# FanControllerSch_Rev2.net
KiCad netlist of a schematic drawn in Altium Designer
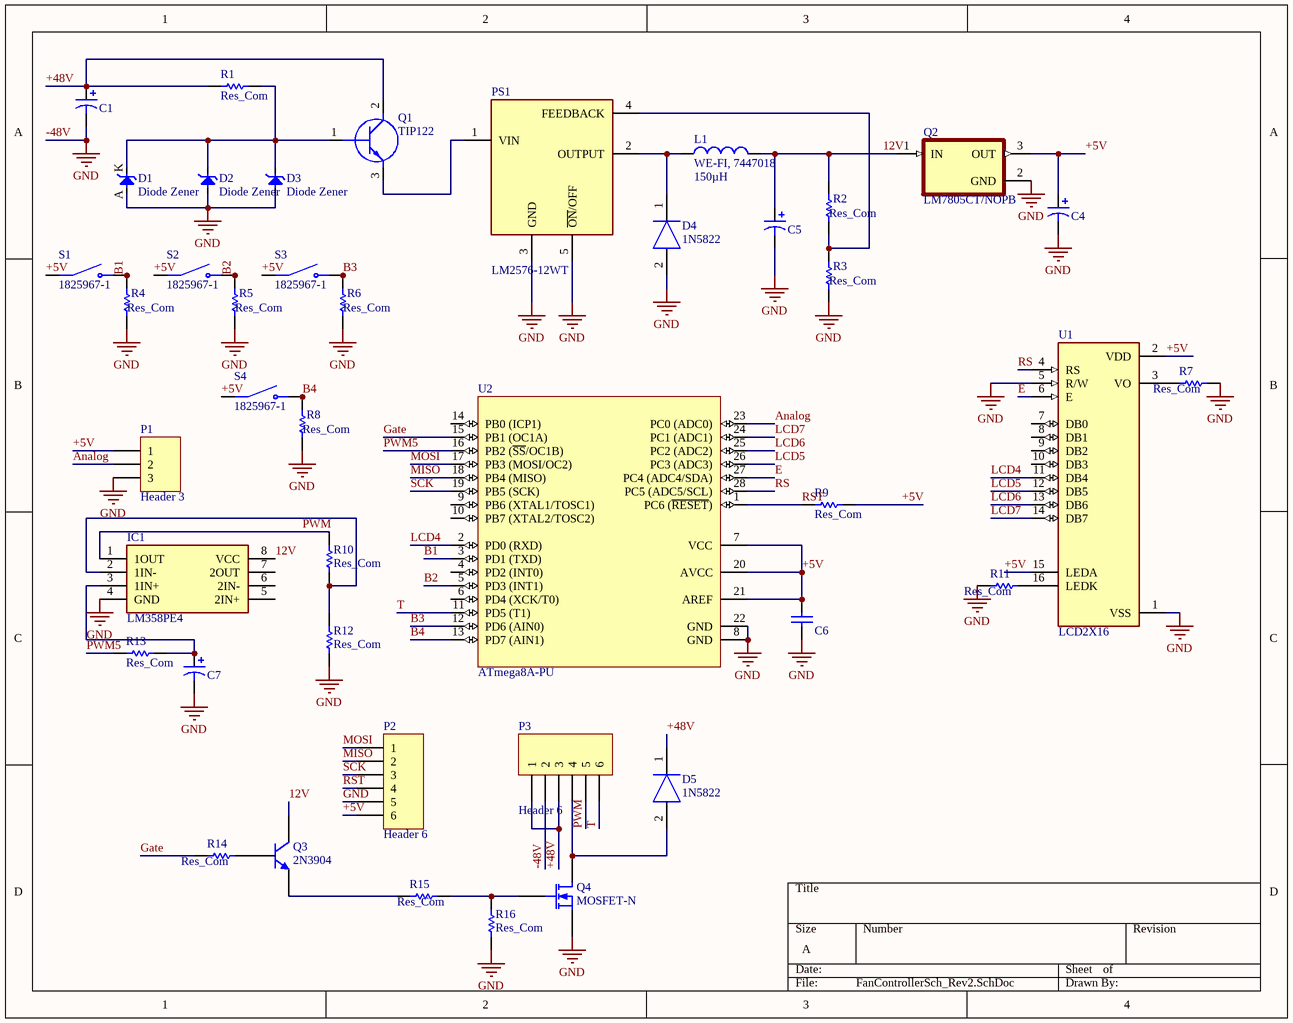
[diagram p0: FanControllerSch_Rev2.SchDoc]

(export (version "E")
  (design (tool "Eeschema 10.0.6"))
  (components
    (comp (ref "C1")
      (value "100 μF")
      (footprint "Radial 12.5 x 25")
      (description "Electrolitic Capacitor, Thru-Hole")
      (fields
        (field (name "PUBLISHER") "Cynetik Group")
        (field (name "CREATED BY") "Zion Blue")
        (field (name "CONTACT") "cynetik_group@hotmail.com")
      )
      (libsource (lib "Capacitors") (part "Electrolitic Capacitor, Thru-Hole"))
    )
    (comp (ref "C4")
      (value "100 μF")
      (footprint "RADIAL 3.5x7.7")
      (description "Electrolitic Capacitor, Thru-Hole")
      (fields
        (field (name "PUBLISHER") "Cynetik Group")
        (field (name "CREATED BY") "Zion Blue")
        (field (name "CONTACT") "cynetik_group@hotmail.com")
      )
      (libsource (lib "Capacitors") (part "Electrolitic Capacitor, Thru-Hole"))
    )
    (comp (ref "C5")
      (value "100 μF")
      (footprint "RADIAL 3.5x7.7")
      (description "Electrolitic Capacitor, Thru-Hole")
      (fields
        (field (name "PUBLISHER") "Cynetik Group")
        (field (name "CREATED BY") "Zion Blue")
        (field (name "CONTACT") "cynetik_group@hotmail.com")
      )
      (libsource (lib "Capacitors") (part "Electrolitic Capacitor, Thru-Hole"))
    )
    (comp (ref "C6")
      (value "100 nF")
      (footprint "Ceramic Capacitor 2")
      (description "Ceramic Capacitor, Thru-Hole")
      (fields
        (field (name "CREATED BY") "Zion Blue")
        (field (name "PUBLISHER") "Cynetik Group")
        (field (name "CONTACT") "cynetik_group@hotmail.com")
      )
      (libsource (lib "Capacitors") (part "Ceramic Capacitor, Thru-Hole."))
    )
    (comp (ref "C7")
      (value "100 μF")
      (footprint "RADIAL 3.5x7.7")
      (description "Electrolitic Capacitor, Thru-Hole")
      (fields
        (field (name "PUBLISHER") "Cynetik Group")
        (field (name "CREATED BY") "Zion Blue")
        (field (name "CONTACT") "cynetik_group@hotmail.com")
      )
      (libsource (lib "Capacitors") (part "Electrolitic Capacitor, Thru-Hole"))
    )
    (comp (ref "D1")
      (value "Diode Zener")
      (footprint "ONSC-AXIAL_LEAD-2-59-10_P")
      (libsource (lib "") (part "Diode Zener_1"))
    )
    (comp (ref "D2")
      (value "Diode Zener")
      (footprint "ONSC-AXIAL_LEAD-2-59-10_P")
      (libsource (lib "Diodes") (part "Diode Zener"))
    )
    (comp (ref "D3")
      (value "Diode Zener")
      (footprint "ONSC-AXIAL_LEAD-2-59-10_P")
      (libsource (lib "Diodes") (part "Diode Zener"))
    )
    (comp (ref "D4")
      (value "1N5822")
      (footprint "ONSC-AXIAL_LEAD-2-59-10_P")
      (description "Diode")
      (libsource (lib "*") (part "1N5822"))
    )
    (comp (ref "D5")
      (value "1N5822")
      (footprint "ONSC-AXIAL_LEAD-2-59-10_P")
      (description "Diode")
      (libsource (lib "*") (part "1N5822"))
    )
    (comp (ref "IC1")
      (value "LM358PE4")
      (footprint "SamacSys:DIP794W53P254L959H508Q8N")
      (description "Integrated Circuit")
      (fields (field (name "MOUSER PART NUMBER") "595-LM358PE4"))
      (libsource (lib "*") (part "LM358PE4"))
    )
    (comp (ref "L1")
      (value "WE-FI, 7447018")
      (footprint "TSL0709RA-102KR19-PF")
      (description "WE-FI Leaded Toroidal Line Choke, L = 150µH")
      (fields
        (field (name "PARTNO") "7447018")
        (field (name "MANUFACTURER") "Wurth Elektronik")
        (field (name "ALTIUM_VALUE") "150µH")
        (field (name "CREATED BY") "Baojun Chen")
      )
      (libsource (lib "Inductor") (part "WE-FI, 7447018"))
    )
    (comp (ref "P1")
      (value "Header 3")
      (footprint "HDR1X3")
      (description "Header, 3-Pin")
      (fields (field (name "PUBLISHER") "Altium Limited"))
      (libsource (lib "Miscellaneous Connectors") (part "Header 3"))
    )
    (comp (ref "P2")
      (value "Header 6")
      (footprint "HDR1X6")
      (description "Header, 6-Pin")
      (fields (field (name "PUBLISHER") "Altium Limited"))
      (libsource (lib "Miscellaneous Connectors") (part "Header 6"))
    )
    (comp (ref "P3")
      (value "Header 6")
      (footprint "HDR1X6")
      (description "Header, 6-Pin")
      (fields (field (name "PUBLISHER") "Altium Limited"))
      (libsource (lib "") (part "Header 6_1"))
    )
    (comp (ref "PS1")
      (value "LM2576-12WT")
      (footprint "SamacSys:TO170P470X1016X1900-5P")
      (description "Power Supply")
      (fields (field (name "MOUSER PART NUMBER") "998-LM2576-12WT"))
      (libsource (lib "*") (part "LM2576-12WT"))
    )
    (comp (ref "Q1")
      (value "TIP122")
      (footprint "SamacSys:TO255P460X1020X2008-3P")
      (description "Transistor BJT NPN")
      (fields (field (name "MOUSER PART NUMBER") "511-TIP122"))
      (libsource (lib "*") (part "TIP122"))
    )
    (comp (ref "Q2")
      (value "LM7805CT/NOPB")
      (footprint "TO254P1054X470X2600-3")
      (description "Linear Voltage Regulator IC 1 Output 1A TO-220-3")
      (fields (field (name "MP") "LM7805CT") (field (name "MF") "ON Semiconductor"))
      (libsource (lib "LDO") (part "LM7805CT/NOPB"))
    )
    (comp (ref "Q3")
      (value "2N3904")
      (footprint "TO-92A")
      (description "NPN General Purpose Amplifier")
      (fields (field (name "PUBLISHER") "Altium Limited"))
      (libsource (lib "Miscellaneous Devices") (part "2N3904"))
    )
    (comp (ref "Q4")
      (value "MOSFET-N")
      (footprint "TO-220AB")
      (description "N-Channel MOSFET")
      (fields (field (name "PUBLISHER") "Altium Limited"))
      (libsource (lib "Miscellaneous Devices") (part "MOSFET-N"))
    )
    (comp (ref "R1")
      (value "Res_Com")
      (footprint "1K Ohm")
      (libsource (lib "Resistors_SMD_IPC-SM-782") (part "Res_Com"))
    )
    (comp (ref "R2")
      (value "Res_Com")
      (footprint "1K Ohm")
      (libsource (lib "Resistors_SMD_IPC-SM-782") (part "Res_Com"))
    )
    (comp (ref "R3")
      (value "Res_Com")
      (footprint "1K Ohm")
      (libsource (lib "Resistors_SMD_IPC-SM-782") (part "Res_Com"))
    )
    (comp (ref "R4")
      (value "Res_Com")
      (footprint "1K Ohm")
      (libsource (lib "Resistors_SMD_IPC-SM-782") (part "Res_Com"))
    )
    (comp (ref "R5")
      (value "Res_Com")
      (footprint "1K Ohm")
      (libsource (lib "Resistors_SMD_IPC-SM-782") (part "Res_Com"))
    )
    (comp (ref "R6")
      (value "Res_Com")
      (footprint "1K Ohm")
      (libsource (lib "Resistors_SMD_IPC-SM-782") (part "Res_Com"))
    )
    (comp (ref "R7")
      (value "Res_Com")
      (footprint "1K Ohm")
      (libsource (lib "Resistors_SMD_IPC-SM-782") (part "Res_Com"))
    )
    (comp (ref "R8")
      (value "Res_Com")
      (footprint "1K Ohm")
      (libsource (lib "Resistors_SMD_IPC-SM-782") (part "Res_Com"))
    )
    (comp (ref "R9")
      (value "Res_Com")
      (footprint "1K Ohm")
      (libsource (lib "Resistors_SMD_IPC-SM-782") (part "Res_Com"))
    )
    (comp (ref "R10")
      (value "Res_Com")
      (footprint "1K Ohm")
      (libsource (lib "Resistors_SMD_IPC-SM-782") (part "Res_Com"))
    )
    (comp (ref "R11")
      (value "Res_Com")
      (footprint "1K Ohm")
      (libsource (lib "Resistors_SMD_IPC-SM-782") (part "Res_Com"))
    )
    (comp (ref "R12")
      (value "Res_Com")
      (footprint "1K Ohm")
      (libsource (lib "Resistors_SMD_IPC-SM-782") (part "Res_Com"))
    )
    (comp (ref "R13")
      (value "Res_Com")
      (footprint "1K Ohm")
      (libsource (lib "Resistors_SMD_IPC-SM-782") (part "Res_Com"))
    )
    (comp (ref "R14")
      (value "Res_Com")
      (footprint "1K Ohm")
      (libsource (lib "Resistors_SMD_IPC-SM-782") (part "Res_Com"))
    )
    (comp (ref "R15")
      (value "Res_Com")
      (footprint "1K Ohm")
      (libsource (lib "Resistors_SMD_IPC-SM-782") (part "Res_Com"))
    )
    (comp (ref "R16")
      (value "Res_Com")
      (footprint "1K Ohm")
      (libsource (lib "Resistors_SMD_IPC-SM-782") (part "Res_Com"))
    )
    (comp (ref "S1")
      (value "1825967-1")
      (footprint "SW_1825967-1")
      (description "Switch Tactile OFF (ON) SPST Round Button PC Pins 0.05A 24VDC 1.57N Thru-Hole")
      (fields
        (field (name "MF") "TE Connectivity")
        (field (name "BUYPART") "https://www.snapeda.com/parts/1825967-1/TE%20Connectivity%20/%20DEUTSCH/view-part/398388/?ref=eda")
      )
      (libsource (lib "1825967-1") (part "1825967-1"))
    )
    (comp (ref "S2")
      (value "1825967-1")
      (footprint "SW_1825967-1")
      (description "Switch Tactile OFF (ON) SPST Round Button PC Pins 0.05A 24VDC 1.57N Thru-Hole")
      (fields
        (field (name "MF") "TE Connectivity")
        (field (name "BUYPART") "https://www.snapeda.com/parts/1825967-1/TE%20Connectivity%20/%20DEUTSCH/view-part/398388/?ref=eda")
      )
      (libsource (lib "1825967-1") (part "1825967-1"))
    )
    (comp (ref "S3")
      (value "1825967-1")
      (footprint "SW_1825967-1")
      (description "Switch Tactile OFF (ON) SPST Round Button PC Pins 0.05A 24VDC 1.57N Thru-Hole")
      (fields
        (field (name "MF") "TE Connectivity")
        (field (name "BUYPART") "https://www.snapeda.com/parts/1825967-1/TE%20Connectivity%20/%20DEUTSCH/view-part/398388/?ref=eda")
      )
      (libsource (lib "1825967-1") (part "1825967-1"))
    )
    (comp (ref "S4")
      (value "1825967-1")
      (footprint "SW_1825967-1")
      (description "Switch Tactile OFF (ON) SPST Round Button PC Pins 0.05A 24VDC 1.57N Thru-Hole")
      (fields
        (field (name "MF") "TE Connectivity")
        (field (name "BUYPART") "https://www.snapeda.com/parts/1825967-1/TE%20Connectivity%20/%20DEUTSCH/view-part/398388/?ref=eda")
      )
      (libsource (lib "1825967-1") (part "1825967-1"))
    )
    (comp (ref "U1")
      (value "LCD2X16")
      (footprint "LCD_LCD2X16")
      (description "Display; Display: LCD 2x16 characters (blue backlight)")
      (fields (field (name "MF") "mikroElektronika"))
      (libsource (lib "LCD2X16") (part "LCD2X16"))
    )
    (comp (ref "U2") (value "ATmega8A-PU") (footprint "28P3") (libsource (lib "ICs") (part "ATmega8A-PU")))
  )
  (nets
    (net (code "1") (name "/+5V") (class "Default")
      (node (ref "C4") (pin "1") (pinfunction "1_1") (pintype "passive"))
      (node (ref "C6") (pin "2") (pinfunction "2_2") (pintype "passive"))
      (node (ref "P1") (pin "1") (pinfunction "1_1") (pintype "passive"))
      (node (ref "P2") (pin "6") (pinfunction "6_6") (pintype "passive"))
      (node (ref "Q2") (pin "3") (pinfunction "OUT_3") (pintype "output"))
      (node (ref "R9") (pin "2") (pinfunction "2_2") (pintype "passive"))
      (node (ref "S1") (pin "1") (pinfunction "COM_1") (pintype "passive"))
      (node (ref "S1") (pin "2") (pinfunction "COM_2") (pintype "passive"))
      (node (ref "S2") (pin "1") (pinfunction "COM_1") (pintype "passive"))
      (node (ref "S2") (pin "2") (pinfunction "COM_2") (pintype "passive"))
      (node (ref "S3") (pin "1") (pinfunction "COM_1") (pintype "passive"))
      (node (ref "S3") (pin "2") (pinfunction "COM_2") (pintype "passive"))
      (node (ref "S4") (pin "1") (pinfunction "COM_1") (pintype "passive"))
      (node (ref "S4") (pin "2") (pinfunction "COM_2") (pintype "passive"))
      (node (ref "U1") (pin "15") (pinfunction "LEDA_15") (pintype "passive"))
      (node (ref "U1") (pin "2") (pinfunction "VDD_2") (pintype "power_in"))
      (node (ref "U2") (pin "20") (pinfunction "AVCC_20") (pintype "power_in"))
      (node (ref "U2") (pin "21") (pinfunction "AREF_21") (pintype "passive"))
      (node (ref "U2") (pin "7") (pinfunction "VCC_7") (pintype "power_in"))
    )
    (net (code "2") (name "/+48V") (class "Default")
      (node (ref "C1") (pin "1") (pinfunction "1_1") (pintype "passive"))
      (node (ref "D5") (pin "1") (pinfunction "K_1") (pintype "passive"))
      (node (ref "P3") (pin "1") (pinfunction "1_1") (pintype "passive"))
      (node (ref "P3") (pin "3") (pinfunction "3_3") (pintype "passive"))
      (node (ref "Q1") (pin "2") (pinfunction "C_2") (pintype "passive"))
      (node (ref "R1") (pin "2") (pinfunction "2_2") (pintype "passive"))
    )
    (net (code "3") (name "/12V") (class "Default")
      (node (ref "C5") (pin "1") (pinfunction "1_1") (pintype "passive"))
      (node (ref "IC1") (pin "8") (pinfunction "VCC_8") (pintype "passive"))
      (node (ref "L1") (pin "2") (pinfunction "2_2") (pintype "passive"))
      (node (ref "Q2") (pin "1") (pinfunction "IN_1") (pintype "input"))
      (node (ref "Q3") (pin "3") (pinfunction "C_3") (pintype "passive"))
      (node (ref "R2") (pin "2") (pinfunction "2_2") (pintype "passive"))
    )
    (net (code "4") (name "/Analog") (class "Default")
      (node (ref "P1") (pin "2") (pinfunction "2_2") (pintype "passive"))
      (node (ref "U2") (pin "23") (pinfunction "PC0_(ADC0)_23") (pintype "bidirectional"))
    )
    (net (code "5") (name "/B1") (class "Default")
      (node (ref "R4") (pin "2") (pinfunction "2_2") (pintype "passive"))
      (node (ref "S1") (pin "3") (pinfunction "NO_3") (pintype "passive"))
      (node (ref "S1") (pin "4") (pinfunction "NO_4") (pintype "passive"))
      (node (ref "U2") (pin "3") (pinfunction "PD1_(TXD)_3") (pintype "bidirectional"))
    )
    (net (code "6") (name "/B2") (class "Default")
      (node (ref "R5") (pin "2") (pinfunction "2_2") (pintype "passive"))
      (node (ref "S2") (pin "3") (pinfunction "NO_3") (pintype "passive"))
      (node (ref "S2") (pin "4") (pinfunction "NO_4") (pintype "passive"))
      (node (ref "U2") (pin "5") (pinfunction "PD3_(INT1)_5") (pintype "bidirectional"))
    )
    (net (code "7") (name "/B3") (class "Default")
      (node (ref "R6") (pin "2") (pinfunction "2_2") (pintype "passive"))
      (node (ref "S3") (pin "3") (pinfunction "NO_3") (pintype "passive"))
      (node (ref "S3") (pin "4") (pinfunction "NO_4") (pintype "passive"))
      (node (ref "U2") (pin "12") (pinfunction "PD6_(AIN0)_12") (pintype "bidirectional"))
    )
    (net (code "8") (name "/B4") (class "Default")
      (node (ref "R8") (pin "2") (pinfunction "2_2") (pintype "passive"))
      (node (ref "S4") (pin "3") (pinfunction "NO_3") (pintype "passive"))
      (node (ref "S4") (pin "4") (pinfunction "NO_4") (pintype "passive"))
      (node (ref "U2") (pin "13") (pinfunction "PD7_(AIN1)_13") (pintype "bidirectional"))
    )
    (net (code "9") (name "/E") (class "Default")
      (node (ref "U1") (pin "6") (pinfunction "E_6") (pintype "input"))
      (node (ref "U2") (pin "27") (pinfunction "PC4_(ADC4/SDA)_27") (pintype "bidirectional"))
    )
    (net (code "10") (name "/Gate") (class "Default")
      (node (ref "R14") (pin "2") (pinfunction "2_2") (pintype "passive"))
      (node (ref "U2") (pin "15") (pinfunction "PB1_(OC1A)_15") (pintype "bidirectional"))
    )
    (net (code "11") (name "/LCD4") (class "Default")
      (node (ref "U1") (pin "11") (pinfunction "DB4_11") (pintype "bidirectional"))
      (node (ref "U2") (pin "2") (pinfunction "PD0_(RXD)_2") (pintype "bidirectional"))
    )
    (net (code "12") (name "/LCD5") (class "Default")
      (node (ref "U1") (pin "12") (pinfunction "DB5_12") (pintype "bidirectional"))
      (node (ref "U2") (pin "26") (pinfunction "PC3_(ADC3)_26") (pintype "bidirectional"))
    )
    (net (code "13") (name "/LCD6") (class "Default")
      (node (ref "U1") (pin "13") (pinfunction "DB6_13") (pintype "bidirectional"))
      (node (ref "U2") (pin "25") (pinfunction "PC2_(ADC2)_25") (pintype "bidirectional"))
    )
    (net (code "14") (name "/LCD7") (class "Default")
      (node (ref "U1") (pin "14") (pinfunction "DB7_14") (pintype "bidirectional"))
      (node (ref "U2") (pin "24") (pinfunction "PC1_(ADC1)_24") (pintype "bidirectional"))
    )
    (net (code "15") (name "/MISO") (class "Default")
      (node (ref "P2") (pin "2") (pinfunction "2_2") (pintype "passive"))
      (node (ref "U2") (pin "18") (pinfunction "PB4_(MISO)_18") (pintype "bidirectional"))
    )
    (net (code "16") (name "/MOSI") (class "Default")
      (node (ref "P2") (pin "1") (pinfunction "1_1") (pintype "passive"))
      (node (ref "U2") (pin "17") (pinfunction "PB3_(MOSI/OC2)_17") (pintype "bidirectional"))
    )
    (net (code "17") (name "/PWM") (class "Default")
      (node (ref "IC1") (pin "1") (pinfunction "1OUT_1") (pintype "passive"))
      (node (ref "P3") (pin "5") (pinfunction "5_5") (pintype "passive"))
      (node (ref "R10") (pin "1") (pinfunction "1_1") (pintype "passive"))
    )
    (net (code "18") (name "/PWM5") (class "Default")
      (node (ref "R13") (pin "2") (pinfunction "2_2") (pintype "passive"))
      (node (ref "U2") (pin "16") (pinfunction "PB2_(~{SS}/OC1B)_16") (pintype "bidirectional"))
    )
    (net (code "19") (name "/RS") (class "Default")
      (node (ref "U1") (pin "4") (pinfunction "RS_4") (pintype "input"))
      (node (ref "U2") (pin "28") (pinfunction "PC5_(ADC5/SCL)_28") (pintype "bidirectional"))
    )
    (net (code "20") (name "/RST") (class "Default")
      (node (ref "P2") (pin "4") (pinfunction "4_4") (pintype "passive"))
      (node (ref "R9") (pin "1") (pinfunction "1_1") (pintype "passive"))
      (node (ref "U2") (pin "1") (pinfunction "PC6_(~{RESET})_1") (pintype "bidirectional"))
    )
    (net (code "21") (name "/SCK") (class "Default")
      (node (ref "P2") (pin "3") (pinfunction "3_3") (pintype "passive"))
      (node (ref "U2") (pin "19") (pinfunction "PB5_(SCK)_19") (pintype "bidirectional"))
    )
    (net (code "22") (name "/T") (class "Default")
      (node (ref "P3") (pin "6") (pinfunction "6_6") (pintype "passive"))
      (node (ref "U2") (pin "11") (pinfunction "PD5_(T1)_11") (pintype "bidirectional"))
    )
    (net (code "23") (name "GND") (class "Default")
      (node (ref "C1") (pin "2") (pinfunction "2_2") (pintype "passive"))
      (node (ref "C4") (pin "2") (pinfunction "2_2") (pintype "passive"))
      (node (ref "C5") (pin "2") (pinfunction "2_2") (pintype "passive"))
      (node (ref "C6") (pin "1") (pinfunction "1_1") (pintype "passive"))
      (node (ref "C7") (pin "2") (pinfunction "2_2") (pintype "passive"))
      (node (ref "D1") (pin "A") (pinfunction "A_A") (pintype "passive"))
      (node (ref "D2") (pin "A") (pinfunction "A_A") (pintype "passive"))
      (node (ref "D3") (pin "A") (pinfunction "A_A") (pintype "passive"))
      (node (ref "D4") (pin "2") (pinfunction "A_2") (pintype "passive"))
      (node (ref "IC1") (pin "4") (pinfunction "GND_4") (pintype "passive"))
      (node (ref "P1") (pin "3") (pinfunction "3_3") (pintype "passive"))
      (node (ref "P2") (pin "5") (pinfunction "5_5") (pintype "passive"))
      (node (ref "P3") (pin "2") (pinfunction "2_2") (pintype "passive"))
      (node (ref "PS1") (pin "3") (pinfunction "GND_3") (pintype "passive"))
      (node (ref "PS1") (pin "5") (pinfunction "~{ON}/OFF_5") (pintype "passive"))
      (node (ref "Q2") (pin "2") (pinfunction "GND_2") (pintype "power_in"))
      (node (ref "Q4") (pin "3") (pinfunction "S_3") (pintype "passive"))
      (node (ref "R11") (pin "2") (pinfunction "2_2") (pintype "passive"))
      (node (ref "R12") (pin "2") (pinfunction "2_2") (pintype "passive"))
      (node (ref "R16") (pin "2") (pinfunction "2_2") (pintype "passive"))
      (node (ref "R3") (pin "1") (pinfunction "1_1") (pintype "passive"))
      (node (ref "R4") (pin "1") (pinfunction "1_1") (pintype "passive"))
      (node (ref "R5") (pin "1") (pinfunction "1_1") (pintype "passive"))
      (node (ref "R6") (pin "1") (pinfunction "1_1") (pintype "passive"))
      (node (ref "R7") (pin "1") (pinfunction "1_1") (pintype "passive"))
      (node (ref "R8") (pin "1") (pinfunction "1_1") (pintype "passive"))
      (node (ref "U1") (pin "1") (pinfunction "VSS_1") (pintype "power_in"))
      (node (ref "U1") (pin "5") (pinfunction "R/W_5") (pintype "input"))
      (node (ref "U2") (pin "22") (pinfunction "GND_22") (pintype "power_in"))
      (node (ref "U2") (pin "8") (pinfunction "GND_8") (pintype "power_in"))
    )
    (net (code "24") (name "Net-(D4-K)") (class "Default")
      (node (ref "D4") (pin "1") (pinfunction "K_1") (pintype "passive"))
      (node (ref "L1") (pin "1") (pinfunction "1_1") (pintype "passive"))
      (node (ref "PS1") (pin "2") (pinfunction "OUTPUT_2") (pintype "passive"))
    )
    (net (code "25") (name "Net-(D5-A)") (class "Default")
      (node (ref "D5") (pin "2") (pinfunction "A_2") (pintype "passive"))
      (node (ref "P3") (pin "4") (pinfunction "4_4") (pintype "passive"))
      (node (ref "Q4") (pin "1") (pinfunction "D_1") (pintype "passive"))
    )
    (net (code "26") (name "Net-(IC1-1IN+)") (class "Default")
      (node (ref "C7") (pin "1") (pinfunction "1_1") (pintype "passive"))
      (node (ref "IC1") (pin "3") (pinfunction "1IN+_3") (pintype "passive"))
      (node (ref "R13") (pin "1") (pinfunction "1_1") (pintype "passive"))
    )
    (net (code "27") (name "Net-(IC1-1IN-)") (class "Default")
      (node (ref "IC1") (pin "2") (pinfunction "1IN-_2") (pintype "passive"))
      (node (ref "R10") (pin "2") (pinfunction "2_2") (pintype "passive"))
      (node (ref "R12") (pin "1") (pinfunction "1_1") (pintype "passive"))
    )
    (net (code "28") (name "Net-(PS1-FEEDBACK)") (class "Default")
      (node (ref "PS1") (pin "4") (pinfunction "FEEDBACK_4") (pintype "passive"))
      (node (ref "R2") (pin "1") (pinfunction "1_1") (pintype "passive"))
      (node (ref "R3") (pin "2") (pinfunction "2_2") (pintype "passive"))
    )
    (net (code "29") (name "Net-(PS1-VIN)") (class "Default")
      (node (ref "PS1") (pin "1") (pinfunction "VIN_1") (pintype "passive"))
      (node (ref "Q1") (pin "3") (pinfunction "E_3") (pintype "passive"))
    )
    (net (code "30") (name "Net-(Q1-B)") (class "Default")
      (node (ref "D1") (pin "K") (pinfunction "K_K") (pintype "passive"))
      (node (ref "D2") (pin "K") (pinfunction "K_K") (pintype "passive"))
      (node (ref "D3") (pin "K") (pinfunction "K_K") (pintype "passive"))
      (node (ref "Q1") (pin "1") (pinfunction "B_1") (pintype "passive"))
      (node (ref "R1") (pin "1") (pinfunction "1_1") (pintype "passive"))
    )
    (net (code "31") (name "Net-(Q3-B)") (class "Default")
      (node (ref "Q3") (pin "2") (pinfunction "B_2") (pintype "passive"))
      (node (ref "R14") (pin "1") (pinfunction "1_1") (pintype "passive"))
    )
    (net (code "32") (name "Net-(Q3-E)") (class "Default")
      (node (ref "Q3") (pin "1") (pinfunction "E_1") (pintype "passive"))
      (node (ref "R15") (pin "2") (pinfunction "2_2") (pintype "passive"))
    )
    (net (code "33") (name "Net-(Q4-G)") (class "Default")
      (node (ref "Q4") (pin "2") (pinfunction "G_2") (pintype "passive"))
      (node (ref "R15") (pin "1") (pinfunction "1_1") (pintype "passive"))
      (node (ref "R16") (pin "1") (pinfunction "1_1") (pintype "passive"))
    )
    (net (code "34") (name "Net-(U1-LEDK)") (class "Default")
      (node (ref "R11") (pin "1") (pinfunction "1_1") (pintype "passive"))
      (node (ref "U1") (pin "16") (pinfunction "LEDK_16") (pintype "passive"))
    )
    (net (code "35") (name "Net-(U1-VO)") (class "Default")
      (node (ref "R7") (pin "2") (pinfunction "2_2") (pintype "passive"))
      (node (ref "U1") (pin "3") (pinfunction "VO_3") (pintype "passive"))
    )
    (net (code "36") (name "unconnected-(IC1-2IN+-Pad5)") (class "Default")
      (node (ref "IC1") (pin "5") (pinfunction "2IN+_5") (pintype "passive"))
    )
    (net (code "37") (name "unconnected-(IC1-2IN--Pad6)") (class "Default")
      (node (ref "IC1") (pin "6") (pinfunction "2IN-_6") (pintype "passive"))
    )
    (net (code "38") (name "unconnected-(IC1-2OUT-Pad7)") (class "Default")
      (node (ref "IC1") (pin "7") (pinfunction "2OUT_7") (pintype "passive"))
    )
    (net (code "39") (name "unconnected-(U1-DB0-Pad7)") (class "Default")
      (node (ref "U1") (pin "7") (pinfunction "DB0_7") (pintype "bidirectional"))
    )
    (net (code "40") (name "unconnected-(U1-DB1-Pad8)") (class "Default")
      (node (ref "U1") (pin "8") (pinfunction "DB1_8") (pintype "bidirectional"))
    )
    (net (code "41") (name "unconnected-(U1-DB2-Pad9)") (class "Default")
      (node (ref "U1") (pin "9") (pinfunction "DB2_9") (pintype "bidirectional"))
    )
    (net (code "42") (name "unconnected-(U1-DB3-Pad10)") (class "Default")
      (node (ref "U1") (pin "10") (pinfunction "DB3_10") (pintype "bidirectional"))
    )
    (net (code "43") (name "unconnected-(U2-PB0_(ICP1)-Pad14)") (class "Default")
      (node (ref "U2") (pin "14") (pinfunction "PB0_(ICP1)_14") (pintype "bidirectional"))
    )
    (net (code "44") (name "unconnected-(U2-PB6_(XTAL1{slash}TOSC1)-Pad9)") (class "Default")
      (node (ref "U2") (pin "9") (pinfunction "PB6_(XTAL1/TOSC1)_9") (pintype "bidirectional"))
    )
    (net (code "45") (name "unconnected-(U2-PB7_(XTAL2{slash}TOSC2)-Pad10)") (class "Default")
      (node (ref "U2") (pin "10") (pinfunction "PB7_(XTAL2/TOSC2)_10") (pintype "bidirectional"))
    )
    (net (code "46") (name "unconnected-(U2-PD2_(INT0)-Pad4)") (class "Default")
      (node (ref "U2") (pin "4") (pinfunction "PD2_(INT0)_4") (pintype "bidirectional"))
    )
    (net (code "47") (name "unconnected-(U2-PD4_(XCK{slash}T0)-Pad6)") (class "Default")
      (node (ref "U2") (pin "6") (pinfunction "PD4_(XCK/T0)_6") (pintype "bidirectional"))
    )
  )
)
